# MCU.net
KiCad netlist of a schematic drawn in Altium Designer
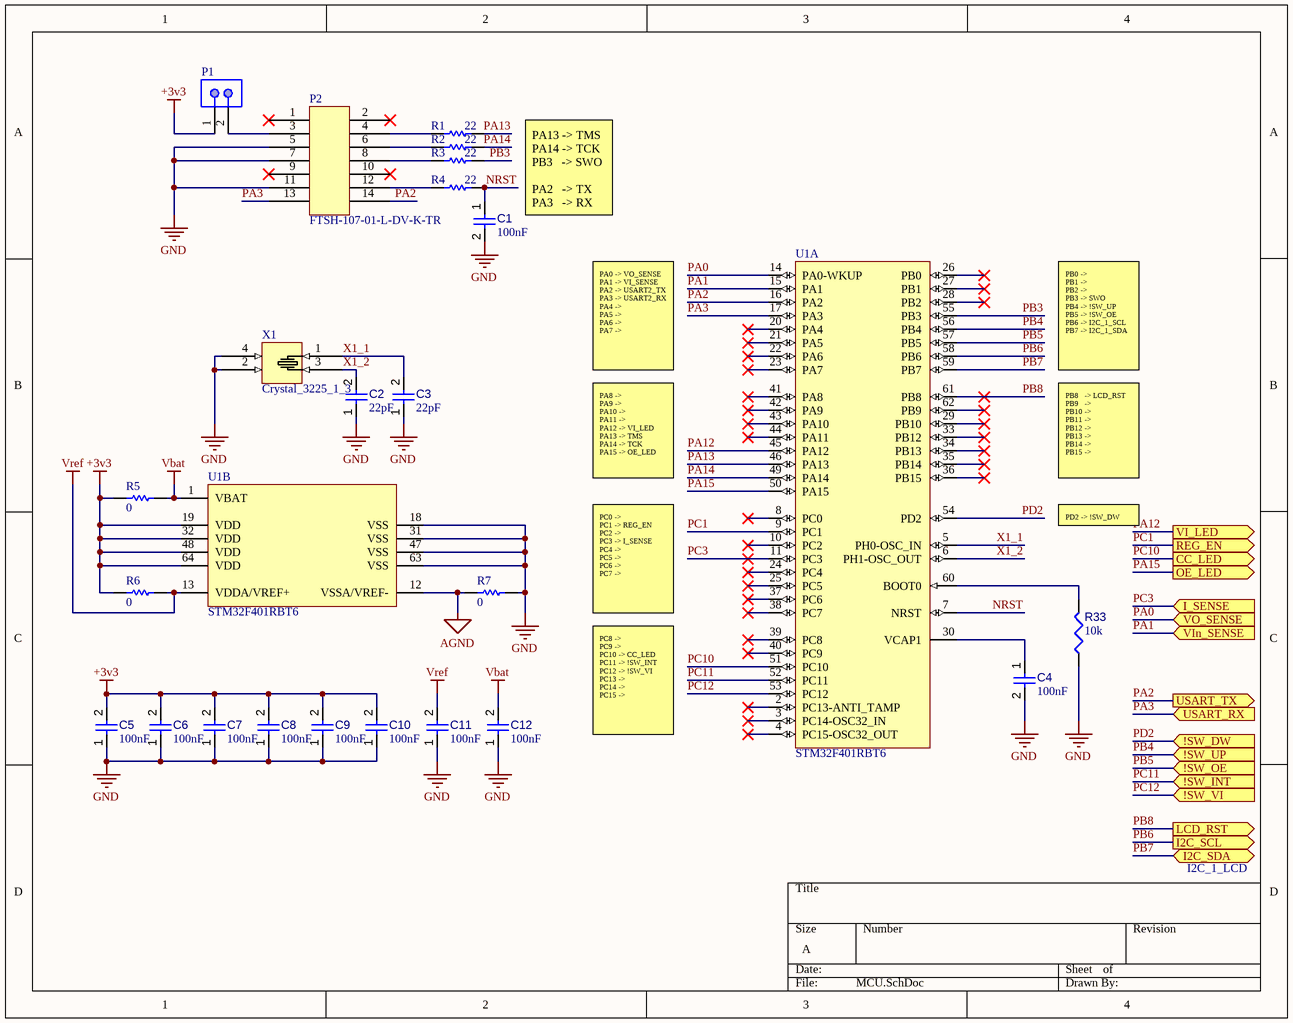
[diagram p0: MCU.SchDoc]

(export (version "E")
  (design (tool "Eeschema 10.0.6"))
  (components
    (comp (ref "C1")
      (value "100nF")
      (footprint "CAPC2013X95X50ML10T25")
      (description "Chip Capacitor, 100 nF, +/- 10%, 50 V, 0805 (2012 Metric)")
      (fields (field (name "TOLERANCE") "10%") (field (name "Comment") "Capacitor 100 nF +/-10% 50 V 0805"))
      (libsource (lib "Aditya Sehgal") (part "CAP-NP-2"))
    )
    (comp (ref "C2")
      (value "22pF")
      (footprint "CAPC2013X95X50ML10T25")
      (description "Chip Capacitor, 100 nF, +/- 10%, 50 V, 0805 (2012 Metric)")
      (fields (field (name "TOLERANCE") "10%") (field (name "Comment") "Capacitor 100 nF +/-10% 50 V 0805"))
      (libsource (lib "Aditya Sehgal") (part "CAP-NP-2"))
    )
    (comp (ref "C3")
      (value "22pF")
      (footprint "CAPC2013X95X50ML10T25")
      (description "Chip Capacitor, 100 nF, +/- 10%, 50 V, 0805 (2012 Metric)")
      (fields (field (name "TOLERANCE") "10%") (field (name "Comment") "Capacitor 100 nF +/-10% 50 V 0805"))
      (libsource (lib "Aditya Sehgal") (part "CAP-NP-2"))
    )
    (comp (ref "C4")
      (value "100nF")
      (footprint "CAPC2013X95X50ML10T25")
      (description "Chip Capacitor, 100 nF, +/- 10%, 50 V, 0805 (2012 Metric)")
      (fields (field (name "TOLERANCE") "10%") (field (name "Comment") "Capacitor 100 nF +/-10% 50 V 0805"))
      (libsource (lib "Aditya Sehgal") (part "CAP-NP-2"))
    )
    (comp (ref "C5")
      (value "100nF")
      (footprint "CAPC2013X95X50ML10T25")
      (description "Chip Capacitor, 100 nF, +/- 10%, 50 V, 0805 (2012 Metric)")
      (fields (field (name "TOLERANCE") "10%") (field (name "Comment") "Capacitor 100 nF +/-10% 50 V 0805"))
      (libsource (lib "Aditya Sehgal") (part "CAP-NP-2"))
    )
    (comp (ref "C6")
      (value "100nF")
      (footprint "CAPC2013X95X50ML10T25")
      (description "Chip Capacitor, 100 nF, +/- 10%, 50 V, 0805 (2012 Metric)")
      (fields (field (name "TOLERANCE") "10%") (field (name "Comment") "Capacitor 100 nF +/-10% 50 V 0805"))
      (libsource (lib "Aditya Sehgal") (part "CAP-NP-2"))
    )
    (comp (ref "C7")
      (value "100nF")
      (footprint "CAPC2013X95X50ML10T25")
      (description "Chip Capacitor, 100 nF, +/- 10%, 50 V, 0805 (2012 Metric)")
      (fields (field (name "TOLERANCE") "10%") (field (name "Comment") "Capacitor 100 nF +/-10% 50 V 0805"))
      (libsource (lib "Aditya Sehgal") (part "CAP-NP-2"))
    )
    (comp (ref "C8")
      (value "100nF")
      (footprint "CAPC2013X95X50ML10T25")
      (description "Chip Capacitor, 100 nF, +/- 10%, 50 V, 0805 (2012 Metric)")
      (fields (field (name "TOLERANCE") "10%") (field (name "Comment") "Capacitor 100 nF +/-10% 50 V 0805"))
      (libsource (lib "Aditya Sehgal") (part "CAP-NP-2"))
    )
    (comp (ref "C9")
      (value "100nF")
      (footprint "CAPC2013X95X50ML10T25")
      (description "Chip Capacitor, 100 nF, +/- 10%, 50 V, 0805 (2012 Metric)")
      (fields (field (name "TOLERANCE") "10%") (field (name "Comment") "Capacitor 100 nF +/-10% 50 V 0805"))
      (libsource (lib "Aditya Sehgal") (part "CAP-NP-2"))
    )
    (comp (ref "C10")
      (value "100nF")
      (footprint "CAPC2013X95X50ML10T25")
      (description "Chip Capacitor, 100 nF, +/- 10%, 50 V, 0805 (2012 Metric)")
      (fields (field (name "TOLERANCE") "10%") (field (name "Comment") "Capacitor 100 nF +/-10% 50 V 0805"))
      (libsource (lib "Aditya Sehgal") (part "CAP-NP-2"))
    )
    (comp (ref "C11")
      (value "100nF")
      (footprint "CAPC2013X95X50ML10T25")
      (description "Chip Capacitor, 100 nF, +/- 10%, 50 V, 0805 (2012 Metric)")
      (fields (field (name "TOLERANCE") "10%") (field (name "Comment") "Capacitor 100 nF +/-10% 50 V 0805"))
      (libsource (lib "Aditya Sehgal") (part "CAP-NP-2"))
    )
    (comp (ref "C12")
      (value "100nF")
      (footprint "CAPC2013X95X50ML10T25")
      (description "Chip Capacitor, 100 nF, +/- 10%, 50 V, 0805 (2012 Metric)")
      (fields (field (name "TOLERANCE") "10%") (field (name "Comment") "Capacitor 100 nF +/-10% 50 V 0805"))
      (libsource (lib "Aditya Sehgal") (part "CAP-NP-2"))
    )
    (comp (ref "P1")
      (value "GRPB021VWVN-RC")
      (footprint "SLIN-GRPB021VWVN-RC_V")
      (fields (field (name "MANUFACTURER") "Sullins"))
      (libsource (lib "Altium Content Vault") (part "CN-1P-M-R2"))
    )
    (comp (ref "P2")
      (value "FTSH-107-01-L-DV-K-TR")
      (footprint "FTSH-107-01-L-DV-K-TR-Footprint-1")
      (description "Conn Unshrouded Header HDR 14 POS 1.27mm Solder ST SMD T/R")
      (libsource (lib "University of California Santa Cruz") (part "FTSH-107-01-L-DV-K-TR"))
    )
    (comp (ref "R1")
      (value "22")
      (footprint "RESC2013X50X35ML15T15")
      (description "Chip Resistor, 0 Ohm, +/- 1%, 125 mW, -55 to 155 degC, 0805 (2012 Metric)")
      (fields (field (name "TOLERANCE") "1%") (field (name "POWER") "125mW"))
      (libsource (lib "Aditya Sehgal") (part "RES-2"))
    )
    (comp (ref "R2")
      (value "22")
      (footprint "RESC2013X50X35ML15T15")
      (description "Chip Resistor, 0 Ohm, +/- 1%, 125 mW, -55 to 155 degC, 0805 (2012 Metric)")
      (fields (field (name "TOLERANCE") "1%") (field (name "POWER") "125mW"))
      (libsource (lib "Aditya Sehgal") (part "RES-2"))
    )
    (comp (ref "R3")
      (value "22")
      (footprint "RESC2013X50X35ML15T15")
      (description "Chip Resistor, 0 Ohm, +/- 1%, 125 mW, -55 to 155 degC, 0805 (2012 Metric)")
      (fields (field (name "TOLERANCE") "1%") (field (name "POWER") "125mW"))
      (libsource (lib "Aditya Sehgal") (part "RES-2"))
    )
    (comp (ref "R4")
      (value "22")
      (footprint "RESC2013X50X35ML15T15")
      (description "Chip Resistor, 0 Ohm, +/- 1%, 125 mW, -55 to 155 degC, 0805 (2012 Metric)")
      (fields (field (name "TOLERANCE") "1%") (field (name "POWER") "125mW"))
      (libsource (lib "Aditya Sehgal") (part "RES-2"))
    )
    (comp (ref "R5")
      (value "0")
      (footprint "RESC2013X50X35ML15T15")
      (description "Chip Resistor, 0 Ohm, +/- 1%, 125 mW, -55 to 155 degC, 0805 (2012 Metric)")
      (fields (field (name "TOLERANCE") "1%") (field (name "POWER") "125mW"))
      (libsource (lib "Aditya Sehgal") (part "RES-2"))
    )
    (comp (ref "R6")
      (value "0")
      (footprint "RESC2013X50X35ML15T15")
      (description "Chip Resistor, 0 Ohm, +/- 1%, 125 mW, -55 to 155 degC, 0805 (2012 Metric)")
      (fields (field (name "TOLERANCE") "1%") (field (name "POWER") "125mW"))
      (libsource (lib "Aditya Sehgal") (part "RES-2"))
    )
    (comp (ref "R7")
      (value "0")
      (footprint "RESC2013X50X35ML15T15")
      (description "Chip Resistor, 0 Ohm, +/- 1%, 125 mW, -55 to 155 degC, 0805 (2012 Metric)")
      (fields (field (name "TOLERANCE") "1%") (field (name "POWER") "125mW"))
      (libsource (lib "Aditya Sehgal") (part "RES-2"))
    )
    (comp (ref "R33")
      (value "10k")
      (footprint "RESC0805(2012)_L")
      (description "Chip Resistor, 470 Ohms, +/-5%, 125 mW, -55 to 155 degC, 0805")
      (fields (field (name "POWER") "125mW") (field (name "TOLERANCE") "5%"))
      (libsource (lib "University of California Santa Cruz") (part "RES-2"))
    )
    (comp (ref "U1")
      (value "STM32F401RBT6")
      (footprint "STM-LQFP64_N")
      (fields (field (name "MANUFACTURER") "STMicroelectronics"))
      (libsource (lib "Altium Content Vault") (part "MC-ARM-STM32F401-SQ64"))
    )
    (comp (ref "X1")
      (value "Crystal_3225_1_3")
      (footprint "Crystal_3225_1_3-Footprint-1")
      (description "3225 crystal")
      (libsource (lib "Aditya Sehgal") (part "Crystal_4pin_1_3"))
    )
  )
  (nets
    (net (code "1") (name "+3v3") (class "Default")
      (node (ref "C10") (pin "2") (pinfunction "2_2") (pintype "passive"))
      (node (ref "C5") (pin "2") (pinfunction "2_2") (pintype "passive"))
      (node (ref "C6") (pin "2") (pinfunction "2_2") (pintype "passive"))
      (node (ref "C7") (pin "2") (pinfunction "2_2") (pintype "passive"))
      (node (ref "C8") (pin "2") (pinfunction "2_2") (pintype "passive"))
      (node (ref "C9") (pin "2") (pinfunction "2_2") (pintype "passive"))
      (node (ref "P1") (pin "1") (pinfunction "1_1") (pintype "passive"))
      (node (ref "R5") (pin "1") (pinfunction "1_1") (pintype "passive"))
      (node (ref "R6") (pin "1") (pinfunction "1_1") (pintype "passive"))
      (node (ref "U1") (pin "19") (pinfunction "VDD_19") (pintype "power_in"))
      (node (ref "U1") (pin "32") (pinfunction "VDD_32") (pintype "power_in"))
      (node (ref "U1") (pin "48") (pinfunction "VDD_48") (pintype "power_in"))
      (node (ref "U1") (pin "64") (pinfunction "VDD_64") (pintype "power_in"))
    )
    (net (code "2") (name "/NRST") (class "Default")
      (node (ref "C1") (pin "1") (pinfunction "1_1") (pintype "passive"))
      (node (ref "R4") (pin "2") (pinfunction "2_2") (pintype "passive"))
      (node (ref "U1") (pin "7") (pinfunction "NRST_7") (pintype "bidirectional"))
    )
    (net (code "3") (name "/PA0") (class "Default")
      (node (ref "U1") (pin "14") (pinfunction "PA0-WKUP_14") (pintype "bidirectional"))
    )
    (net (code "4") (name "/PA1") (class "Default")
      (node (ref "U1") (pin "15") (pinfunction "PA1_15") (pintype "bidirectional"))
    )
    (net (code "5") (name "/PA2") (class "Default")
      (node (ref "P2") (pin "14") (pinfunction "14_14") (pintype "passive"))
      (node (ref "U1") (pin "16") (pinfunction "PA2_16") (pintype "bidirectional"))
    )
    (net (code "6") (name "/PA3") (class "Default")
      (node (ref "P2") (pin "13") (pinfunction "13_13") (pintype "passive"))
      (node (ref "U1") (pin "17") (pinfunction "PA3_17") (pintype "bidirectional"))
    )
    (net (code "7") (name "/PA12") (class "Default")
      (node (ref "U1") (pin "45") (pinfunction "PA12_45") (pintype "bidirectional"))
    )
    (net (code "8") (name "/PA13") (class "Default")
      (node (ref "R1") (pin "2") (pinfunction "2_2") (pintype "passive"))
      (node (ref "U1") (pin "46") (pinfunction "PA13_46") (pintype "bidirectional"))
    )
    (net (code "9") (name "/PA14") (class "Default")
      (node (ref "R2") (pin "2") (pinfunction "2_2") (pintype "passive"))
      (node (ref "U1") (pin "49") (pinfunction "PA14_49") (pintype "bidirectional"))
    )
    (net (code "10") (name "/PA15") (class "Default")
      (node (ref "U1") (pin "50") (pinfunction "PA15_50") (pintype "bidirectional"))
    )
    (net (code "11") (name "/PB3") (class "Default")
      (node (ref "R3") (pin "2") (pinfunction "2_2") (pintype "passive"))
      (node (ref "U1") (pin "55") (pinfunction "PB3_55") (pintype "bidirectional"))
    )
    (net (code "12") (name "/PB4") (class "Default")
      (node (ref "U1") (pin "56") (pinfunction "PB4_56") (pintype "bidirectional"))
    )
    (net (code "13") (name "/PB5") (class "Default")
      (node (ref "U1") (pin "57") (pinfunction "PB5_57") (pintype "bidirectional"))
    )
    (net (code "14") (name "/PB6") (class "Default")
      (node (ref "U1") (pin "58") (pinfunction "PB6_58") (pintype "bidirectional"))
    )
    (net (code "15") (name "/PB7") (class "Default")
      (node (ref "U1") (pin "59") (pinfunction "PB7_59") (pintype "bidirectional"))
    )
    (net (code "16") (name "/PB8") (class "Default")
      (node (ref "U1") (pin "61") (pinfunction "PB8_61") (pintype "bidirectional"))
    )
    (net (code "17") (name "/PC1") (class "Default")
      (node (ref "U1") (pin "9") (pinfunction "PC1_9") (pintype "bidirectional"))
    )
    (net (code "18") (name "/PC3") (class "Default")
      (node (ref "U1") (pin "11") (pinfunction "PC3_11") (pintype "bidirectional"))
    )
    (net (code "19") (name "/PC10") (class "Default")
      (node (ref "U1") (pin "51") (pinfunction "PC10_51") (pintype "bidirectional"))
    )
    (net (code "20") (name "/PC11") (class "Default")
      (node (ref "U1") (pin "52") (pinfunction "PC11_52") (pintype "bidirectional"))
    )
    (net (code "21") (name "/PC12") (class "Default")
      (node (ref "U1") (pin "53") (pinfunction "PC12_53") (pintype "bidirectional"))
    )
    (net (code "22") (name "/PD2") (class "Default")
      (node (ref "U1") (pin "54") (pinfunction "PD2_54") (pintype "bidirectional"))
    )
    (net (code "23") (name "/X1_1") (class "Default")
      (node (ref "C3") (pin "2") (pinfunction "2_2") (pintype "passive"))
      (node (ref "U1") (pin "5") (pinfunction "PH0-OSC_IN_5") (pintype "bidirectional"))
      (node (ref "X1") (pin "1") (pinfunction "X1_1") (pintype "input"))
    )
    (net (code "24") (name "/X1_2") (class "Default")
      (node (ref "C2") (pin "2") (pinfunction "2_2") (pintype "passive"))
      (node (ref "U1") (pin "6") (pinfunction "PH1-OSC_OUT_6") (pintype "bidirectional"))
      (node (ref "X1") (pin "3") (pinfunction "X2_3") (pintype "input"))
    )
    (net (code "25") (name "AGND") (class "Default")
      (node (ref "R7") (pin "1") (pinfunction "1_1") (pintype "passive"))
      (node (ref "U1") (pin "12") (pinfunction "VSSA/VREF-_12") (pintype "power_in"))
    )
    (net (code "26") (name "GND") (class "Default")
      (node (ref "C1") (pin "2") (pinfunction "2_2") (pintype "passive"))
      (node (ref "C10") (pin "1") (pinfunction "1_1") (pintype "passive"))
      (node (ref "C11") (pin "1") (pinfunction "1_1") (pintype "passive"))
      (node (ref "C12") (pin "1") (pinfunction "1_1") (pintype "passive"))
      (node (ref "C2") (pin "1") (pinfunction "1_1") (pintype "passive"))
      (node (ref "C3") (pin "1") (pinfunction "1_1") (pintype "passive"))
      (node (ref "C4") (pin "2") (pinfunction "2_2") (pintype "passive"))
      (node (ref "C5") (pin "1") (pinfunction "1_1") (pintype "passive"))
      (node (ref "C6") (pin "1") (pinfunction "1_1") (pintype "passive"))
      (node (ref "C7") (pin "1") (pinfunction "1_1") (pintype "passive"))
      (node (ref "C8") (pin "1") (pinfunction "1_1") (pintype "passive"))
      (node (ref "C9") (pin "1") (pinfunction "1_1") (pintype "passive"))
      (node (ref "P2") (pin "11") (pinfunction "11_11") (pintype "passive"))
      (node (ref "P2") (pin "5") (pinfunction "5_5") (pintype "passive"))
      (node (ref "P2") (pin "7") (pinfunction "7_7") (pintype "passive"))
      (node (ref "R33") (pin "1") (pinfunction "1_1") (pintype "passive"))
      (node (ref "R7") (pin "2") (pinfunction "2_2") (pintype "passive"))
      (node (ref "U1") (pin "18") (pinfunction "VSS_18") (pintype "power_in"))
      (node (ref "U1") (pin "31") (pinfunction "VSS_31") (pintype "power_in"))
      (node (ref "U1") (pin "47") (pinfunction "VSS_47") (pintype "power_in"))
      (node (ref "U1") (pin "63") (pinfunction "VSS_63") (pintype "power_in"))
      (node (ref "X1") (pin "2") (pinfunction "GND_2") (pintype "input"))
      (node (ref "X1") (pin "4") (pinfunction "GND_4") (pintype "input"))
    )
    (net (code "27") (name "Net-(P1-Pad2)") (class "Default")
      (node (ref "P1") (pin "2") (pinfunction "2_2") (pintype "passive"))
      (node (ref "P2") (pin "3") (pinfunction "3_3") (pintype "passive"))
    )
    (net (code "28") (name "Net-(P2-Pad4)") (class "Default")
      (node (ref "P2") (pin "4") (pinfunction "4_4") (pintype "passive"))
      (node (ref "R1") (pin "1") (pinfunction "1_1") (pintype "passive"))
    )
    (net (code "29") (name "Net-(P2-Pad6)") (class "Default")
      (node (ref "P2") (pin "6") (pinfunction "6_6") (pintype "passive"))
      (node (ref "R2") (pin "1") (pinfunction "1_1") (pintype "passive"))
    )
    (net (code "30") (name "Net-(P2-Pad8)") (class "Default")
      (node (ref "P2") (pin "8") (pinfunction "8_8") (pintype "passive"))
      (node (ref "R3") (pin "1") (pinfunction "1_1") (pintype "passive"))
    )
    (net (code "31") (name "Net-(P2-Pad12)") (class "Default")
      (node (ref "P2") (pin "12") (pinfunction "12_12") (pintype "passive"))
      (node (ref "R4") (pin "1") (pinfunction "1_1") (pintype "passive"))
    )
    (net (code "32") (name "Net-(U1A-BOOT0)") (class "Default")
      (node (ref "R33") (pin "2") (pinfunction "2_2") (pintype "passive"))
      (node (ref "U1") (pin "60") (pinfunction "BOOT0_60") (pintype "input"))
    )
    (net (code "33") (name "Net-(U1A-VCAP1)") (class "Default")
      (node (ref "C4") (pin "1") (pinfunction "1_1") (pintype "passive"))
      (node (ref "U1") (pin "30") (pinfunction "VCAP1_30") (pintype "power_in"))
    )
    (net (code "34") (name "Vbat") (class "Default")
      (node (ref "C12") (pin "2") (pinfunction "2_2") (pintype "passive"))
      (node (ref "R5") (pin "2") (pinfunction "2_2") (pintype "passive"))
      (node (ref "U1") (pin "1") (pinfunction "VBAT_1") (pintype "power_in"))
    )
    (net (code "35") (name "Vref") (class "Default")
      (node (ref "C11") (pin "2") (pinfunction "2_2") (pintype "passive"))
      (node (ref "R6") (pin "2") (pinfunction "2_2") (pintype "passive"))
      (node (ref "U1") (pin "13") (pinfunction "VDDA/VREF+_13") (pintype "power_in"))
    )
    (net (code "36") (name "unconnected-(P2-Pad1)") (class "Default")
      (node (ref "P2") (pin "1") (pinfunction "1_1") (pintype "passive+no_connect"))
    )
    (net (code "37") (name "unconnected-(P2-Pad2)") (class "Default")
      (node (ref "P2") (pin "2") (pinfunction "2_2") (pintype "passive+no_connect"))
    )
    (net (code "38") (name "unconnected-(P2-Pad9)") (class "Default")
      (node (ref "P2") (pin "9") (pinfunction "9_9") (pintype "passive+no_connect"))
    )
    (net (code "39") (name "unconnected-(P2-Pad10)") (class "Default")
      (node (ref "P2") (pin "10") (pinfunction "10_10") (pintype "passive+no_connect"))
    )
    (net (code "40") (name "unconnected-(U1A-PA4-Pad20)") (class "Default")
      (node (ref "U1") (pin "20") (pinfunction "PA4_20") (pintype "bidirectional+no_connect"))
    )
    (net (code "41") (name "unconnected-(U1A-PA5-Pad21)") (class "Default")
      (node (ref "U1") (pin "21") (pinfunction "PA5_21") (pintype "bidirectional+no_connect"))
    )
    (net (code "42") (name "unconnected-(U1A-PA6-Pad22)") (class "Default")
      (node (ref "U1") (pin "22") (pinfunction "PA6_22") (pintype "bidirectional+no_connect"))
    )
    (net (code "43") (name "unconnected-(U1A-PA7-Pad23)") (class "Default")
      (node (ref "U1") (pin "23") (pinfunction "PA7_23") (pintype "bidirectional+no_connect"))
    )
    (net (code "44") (name "unconnected-(U1A-PA8-Pad41)") (class "Default")
      (node (ref "U1") (pin "41") (pinfunction "PA8_41") (pintype "bidirectional+no_connect"))
    )
    (net (code "45") (name "unconnected-(U1A-PA9-Pad42)") (class "Default")
      (node (ref "U1") (pin "42") (pinfunction "PA9_42") (pintype "bidirectional+no_connect"))
    )
    (net (code "46") (name "unconnected-(U1A-PA10-Pad43)") (class "Default")
      (node (ref "U1") (pin "43") (pinfunction "PA10_43") (pintype "bidirectional+no_connect"))
    )
    (net (code "47") (name "unconnected-(U1A-PA11-Pad44)") (class "Default")
      (node (ref "U1") (pin "44") (pinfunction "PA11_44") (pintype "bidirectional+no_connect"))
    )
    (net (code "48") (name "unconnected-(U1A-PB0-Pad26)") (class "Default")
      (node (ref "U1") (pin "26") (pinfunction "PB0_26") (pintype "bidirectional+no_connect"))
    )
    (net (code "49") (name "unconnected-(U1A-PB1-Pad27)") (class "Default")
      (node (ref "U1") (pin "27") (pinfunction "PB1_27") (pintype "bidirectional+no_connect"))
    )
    (net (code "50") (name "unconnected-(U1A-PB2-Pad28)") (class "Default")
      (node (ref "U1") (pin "28") (pinfunction "PB2_28") (pintype "bidirectional+no_connect"))
    )
    (net (code "51") (name "unconnected-(U1A-PB9-Pad62)") (class "Default")
      (node (ref "U1") (pin "62") (pinfunction "PB9_62") (pintype "bidirectional+no_connect"))
    )
    (net (code "52") (name "unconnected-(U1A-PB10-Pad29)") (class "Default")
      (node (ref "U1") (pin "29") (pinfunction "PB10_29") (pintype "bidirectional+no_connect"))
    )
    (net (code "53") (name "unconnected-(U1A-PB12-Pad33)") (class "Default")
      (node (ref "U1") (pin "33") (pinfunction "PB12_33") (pintype "bidirectional+no_connect"))
    )
    (net (code "54") (name "unconnected-(U1A-PB13-Pad34)") (class "Default")
      (node (ref "U1") (pin "34") (pinfunction "PB13_34") (pintype "bidirectional+no_connect"))
    )
    (net (code "55") (name "unconnected-(U1A-PB14-Pad35)") (class "Default")
      (node (ref "U1") (pin "35") (pinfunction "PB14_35") (pintype "bidirectional+no_connect"))
    )
    (net (code "56") (name "unconnected-(U1A-PB15-Pad36)") (class "Default")
      (node (ref "U1") (pin "36") (pinfunction "PB15_36") (pintype "bidirectional+no_connect"))
    )
    (net (code "57") (name "unconnected-(U1A-PC0-Pad8)") (class "Default")
      (node (ref "U1") (pin "8") (pinfunction "PC0_8") (pintype "bidirectional+no_connect"))
    )
    (net (code "58") (name "unconnected-(U1A-PC2-Pad10)") (class "Default")
      (node (ref "U1") (pin "10") (pinfunction "PC2_10") (pintype "bidirectional+no_connect"))
    )
    (net (code "59") (name "unconnected-(U1A-PC4-Pad24)") (class "Default")
      (node (ref "U1") (pin "24") (pinfunction "PC4_24") (pintype "bidirectional+no_connect"))
    )
    (net (code "60") (name "unconnected-(U1A-PC5-Pad25)") (class "Default")
      (node (ref "U1") (pin "25") (pinfunction "PC5_25") (pintype "bidirectional+no_connect"))
    )
    (net (code "61") (name "unconnected-(U1A-PC6-Pad37)") (class "Default")
      (node (ref "U1") (pin "37") (pinfunction "PC6_37") (pintype "bidirectional+no_connect"))
    )
    (net (code "62") (name "unconnected-(U1A-PC7-Pad38)") (class "Default")
      (node (ref "U1") (pin "38") (pinfunction "PC7_38") (pintype "bidirectional+no_connect"))
    )
    (net (code "63") (name "unconnected-(U1A-PC8-Pad39)") (class "Default")
      (node (ref "U1") (pin "39") (pinfunction "PC8_39") (pintype "bidirectional+no_connect"))
    )
    (net (code "64") (name "unconnected-(U1A-PC9-Pad40)") (class "Default")
      (node (ref "U1") (pin "40") (pinfunction "PC9_40") (pintype "bidirectional+no_connect"))
    )
    (net (code "65") (name "unconnected-(U1A-PC13-ANTI_TAMP-Pad2)") (class "Default")
      (node (ref "U1") (pin "2") (pinfunction "PC13-ANTI_TAMP_2") (pintype "bidirectional+no_connect"))
    )
    (net (code "66") (name "unconnected-(U1A-PC14-OSC32_IN-Pad3)") (class "Default")
      (node (ref "U1") (pin "3") (pinfunction "PC14-OSC32_IN_3") (pintype "bidirectional+no_connect"))
    )
    (net (code "67") (name "unconnected-(U1A-PC15-OSC32_OUT-Pad4)") (class "Default")
      (node (ref "U1") (pin "4") (pinfunction "PC15-OSC32_OUT_4") (pintype "bidirectional+no_connect"))
    )
  )
)
